# POWER.net
KiCad netlist of a schematic drawn in Altium Designer
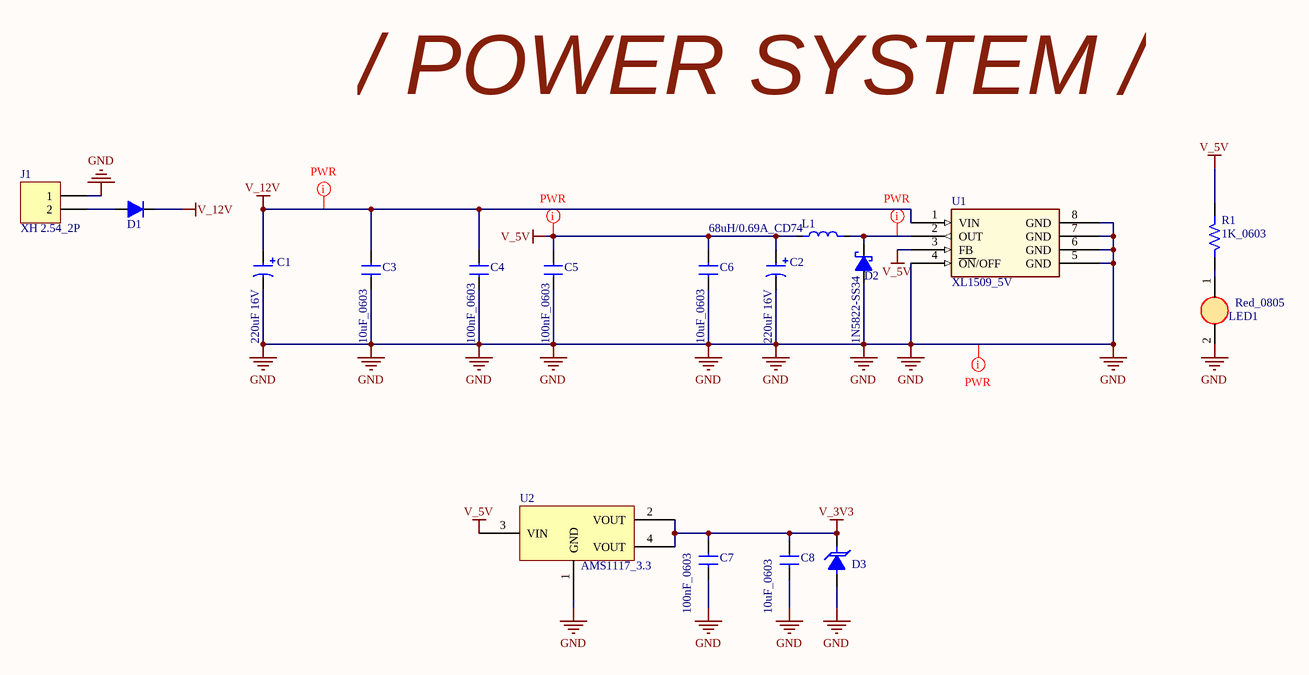
[diagram p0: POWER.SchDoc]

(export (version "E")
  (design (tool "Eeschema 10.0.6"))
  (components
    (comp (ref "C1")
      (value "220uF 16V")
      (footprint "CAP-ALU-SMD-6.3x7.7")
      (description "6.3 x 7, CAP ALU")
      (libsource (lib "LYAM_LIB") (part "CAP ALU 220uF 16V"))
    )
    (comp (ref "C2")
      (value "220uF 16V")
      (footprint "CAP-ALU-SMD-6.3x7.7")
      (description "6.3 x 7, CAP ALU")
      (libsource (lib "LYAM_LIB") (part "CAP ALU 220uF 16V"))
    )
    (comp (ref "C3")
      (value "10uF_0603")
      (footprint "CN-SMD-0603")
      (description "Cap SMD, 0.06x0.03 inch, 1.55x0.85 mm - 1608")
      (libsource (lib "LYAM_LIB") (part "CAP 0603 106"))
    )
    (comp (ref "C4")
      (value "100nF_0603")
      (footprint "CN-SMD-0603")
      (description "Cap SMD, 0.06x0.03 inch, 1.55x0.85 mm - 1608")
      (libsource (lib "LYAM_LIB") (part "CAP 0603 104"))
    )
    (comp (ref "C5")
      (value "100nF_0603")
      (footprint "CN-SMD-0603")
      (description "Cap SMD, 0.06x0.03 inch, 1.55x0.85 mm - 1608")
      (libsource (lib "LYAM_LIB") (part "CAP 0603 104"))
    )
    (comp (ref "C6")
      (value "10uF_0603")
      (footprint "CN-SMD-0603")
      (description "Cap SMD, 0.06x0.03 inch, 1.55x0.85 mm - 1608")
      (libsource (lib "LYAM_LIB") (part "CAP 0603 106"))
    )
    (comp (ref "C7")
      (value "100nF_0603")
      (footprint "CN-SMD-0603")
      (description "Cap SMD, 0.06x0.03 inch, 1.55x0.85 mm - 1608")
      (libsource (lib "LYAM_LIB") (part "CAP 0603 104"))
    )
    (comp (ref "C8")
      (value "10uF_0603")
      (footprint "CN-SMD-0603")
      (description "Cap SMD, 0.06x0.03 inch, 1.55x0.85 mm - 1608")
      (libsource (lib "LYAM_LIB") (part "CAP 0603 106"))
    )
    (comp (ref "D1")
      (value "1N5408-S3M")
      (footprint "SMA")
      (description "Power Diode 3A, VRRM ~ 1000V")
      (fields (field (name "PUBLISHER") "Altium Limited"))
      (libsource (lib "LYAM_LIB") (part "Diode 1N5408 S3M"))
    )
    (comp (ref "D2")
      (value "1N5822-SS34")
      (footprint "SMA")
      (description "Schottky diode, 3A, VRRM 40V")
      (fields (field (name "PUBLISHER") "Altium Limited"))
      (libsource (lib "Passive_MKB") (part "Diode 1N5822 SS34"))
    )
    (comp (ref "D3")
      (value "SMBJ5.0A_KE")
      (footprint "SMB")
      (description "TVS Diode, Vrrm =5.0V, Vcl = 9.2V")
      (fields (field (name "PUBLISHER") "Altium Limited"))
      (libsource (lib "LYAM_LIB") (part "Diode SMBJ5.0A"))
    )
    (comp (ref "J1")
      (value "XH 2.54_2P")
      (footprint "Header2")
      (libsource (lib "LYAM_LIB") (part "XH 2.54_2P"))
    )
    (comp (ref "L1")
      (value "68uH/0.69A_CD74")
      (footprint "INDUCTOR_CD74")
      (description "SMD Power Inductor SMD Power Inductor\r\nCDRH74")
      (libsource (lib "LYAM_LIB") (part "CD74 680"))
    )
    (comp (ref "LED1")
      (value "Red_0805")
      (footprint "LED-0805-Red")
      (description "LED SMD")
      (libsource (lib "Passive_MKB") (part "LED 0805 RED"))
    )
    (comp (ref "R1")
      (value "1K_0603")
      (footprint "RES-SMD-0603")
      (description "Resistor SMD, 0.06x0.03 inch, 1.55x0.85 mm - 1608, 1/10W")
      (libsource (lib "LYAM_LIB") (part "RES 0603 1K"))
    )
    (comp (ref "U1") (value "XL1509_5V") (footprint "SO8") (libsource (lib "IC_MKB") (part "XL1509_5V")))
    (comp (ref "U2")
      (value "AMS1117_3.3")
      (footprint "SOT223-4N")
      (description "AMS1117_SOT223_3V3, 1.4A, Vin = 18V")
      (libsource (lib "LYAM_LIB") (part "AMS1117_SOT223_3V3"))
    )
  )
  (nets
    (net (code "1") (name "GND") (class "Default")
      (node (ref "C1") (pin "2") (pinfunction "2_2") (pintype "passive"))
      (node (ref "C2") (pin "2") (pinfunction "2_2") (pintype "passive"))
      (node (ref "C3") (pin "1") (pinfunction "1_1") (pintype "passive"))
      (node (ref "C4") (pin "1") (pinfunction "1_1") (pintype "passive"))
      (node (ref "C5") (pin "1") (pinfunction "1_1") (pintype "passive"))
      (node (ref "C6") (pin "1") (pinfunction "1_1") (pintype "passive"))
      (node (ref "C7") (pin "1") (pinfunction "1_1") (pintype "passive"))
      (node (ref "C8") (pin "1") (pinfunction "1_1") (pintype "passive"))
      (node (ref "D2") (pin "1") (pinfunction "A_1") (pintype "passive"))
      (node (ref "D3") (pin "1") (pinfunction "A_1") (pintype "passive"))
      (node (ref "J1") (pin "1") (pinfunction "1_1") (pintype "passive"))
      (node (ref "LED1") (pin "2") (pinfunction "K_2") (pintype "passive"))
      (node (ref "U1") (pin "4") (pinfunction "~{ON}/OFF_4") (pintype "input"))
      (node (ref "U1") (pin "5") (pinfunction "GND_5") (pintype "passive"))
      (node (ref "U1") (pin "6") (pinfunction "GND_6") (pintype "passive"))
      (node (ref "U1") (pin "7") (pinfunction "GND_7") (pintype "passive"))
      (node (ref "U1") (pin "8") (pinfunction "GND_8") (pintype "passive"))
      (node (ref "U2") (pin "1") (pinfunction "GND_1") (pintype "passive"))
    )
    (net (code "2") (name "Net-(D1-A)") (class "Default")
      (node (ref "D1") (pin "1") (pinfunction "A_1") (pintype "passive"))
      (node (ref "J1") (pin "2") (pinfunction "2_2") (pintype "passive"))
    )
    (net (code "3") (name "Net-(D2-K)") (class "Default")
      (node (ref "D2") (pin "2") (pinfunction "K_2") (pintype "passive"))
      (node (ref "L1") (pin "2") (pinfunction "2_2") (pintype "passive"))
      (node (ref "U1") (pin "2") (pinfunction "OUT_2") (pintype "output"))
    )
    (net (code "4") (name "Net-(LED1-A)") (class "Default")
      (node (ref "LED1") (pin "1") (pinfunction "A_1") (pintype "passive"))
      (node (ref "R1") (pin "1") (pinfunction "1_1") (pintype "passive"))
    )
    (net (code "5") (name "V_3V3") (class "Default")
      (node (ref "C7") (pin "2") (pinfunction "2_2") (pintype "passive"))
      (node (ref "C8") (pin "2") (pinfunction "2_2") (pintype "passive"))
      (node (ref "D3") (pin "2") (pinfunction "K_2") (pintype "passive"))
      (node (ref "U2") (pin "2") (pinfunction "VOUT_2") (pintype "passive"))
      (node (ref "U2") (pin "4") (pinfunction "VOUT_4") (pintype "passive"))
    )
    (net (code "6") (name "V_5V") (class "Default")
      (node (ref "C2") (pin "1") (pinfunction "1_1") (pintype "passive"))
      (node (ref "C5") (pin "2") (pinfunction "2_2") (pintype "passive"))
      (node (ref "C6") (pin "2") (pinfunction "2_2") (pintype "passive"))
      (node (ref "L1") (pin "1") (pinfunction "1_1") (pintype "passive"))
      (node (ref "R1") (pin "2") (pinfunction "2_2") (pintype "passive"))
      (node (ref "U1") (pin "3") (pinfunction "FB_3") (pintype "input"))
      (node (ref "U2") (pin "3") (pinfunction "VIN_3") (pintype "passive"))
    )
    (net (code "7") (name "V_12V") (class "Default")
      (node (ref "C1") (pin "1") (pinfunction "1_1") (pintype "passive"))
      (node (ref "C3") (pin "2") (pinfunction "2_2") (pintype "passive"))
      (node (ref "C4") (pin "2") (pinfunction "2_2") (pintype "passive"))
      (node (ref "D1") (pin "2") (pinfunction "K_2") (pintype "passive"))
      (node (ref "U1") (pin "1") (pinfunction "VIN_1") (pintype "input"))
    )
  )
)
